# IM.net
KiCad netlist of a schematic drawn in Altium Designer
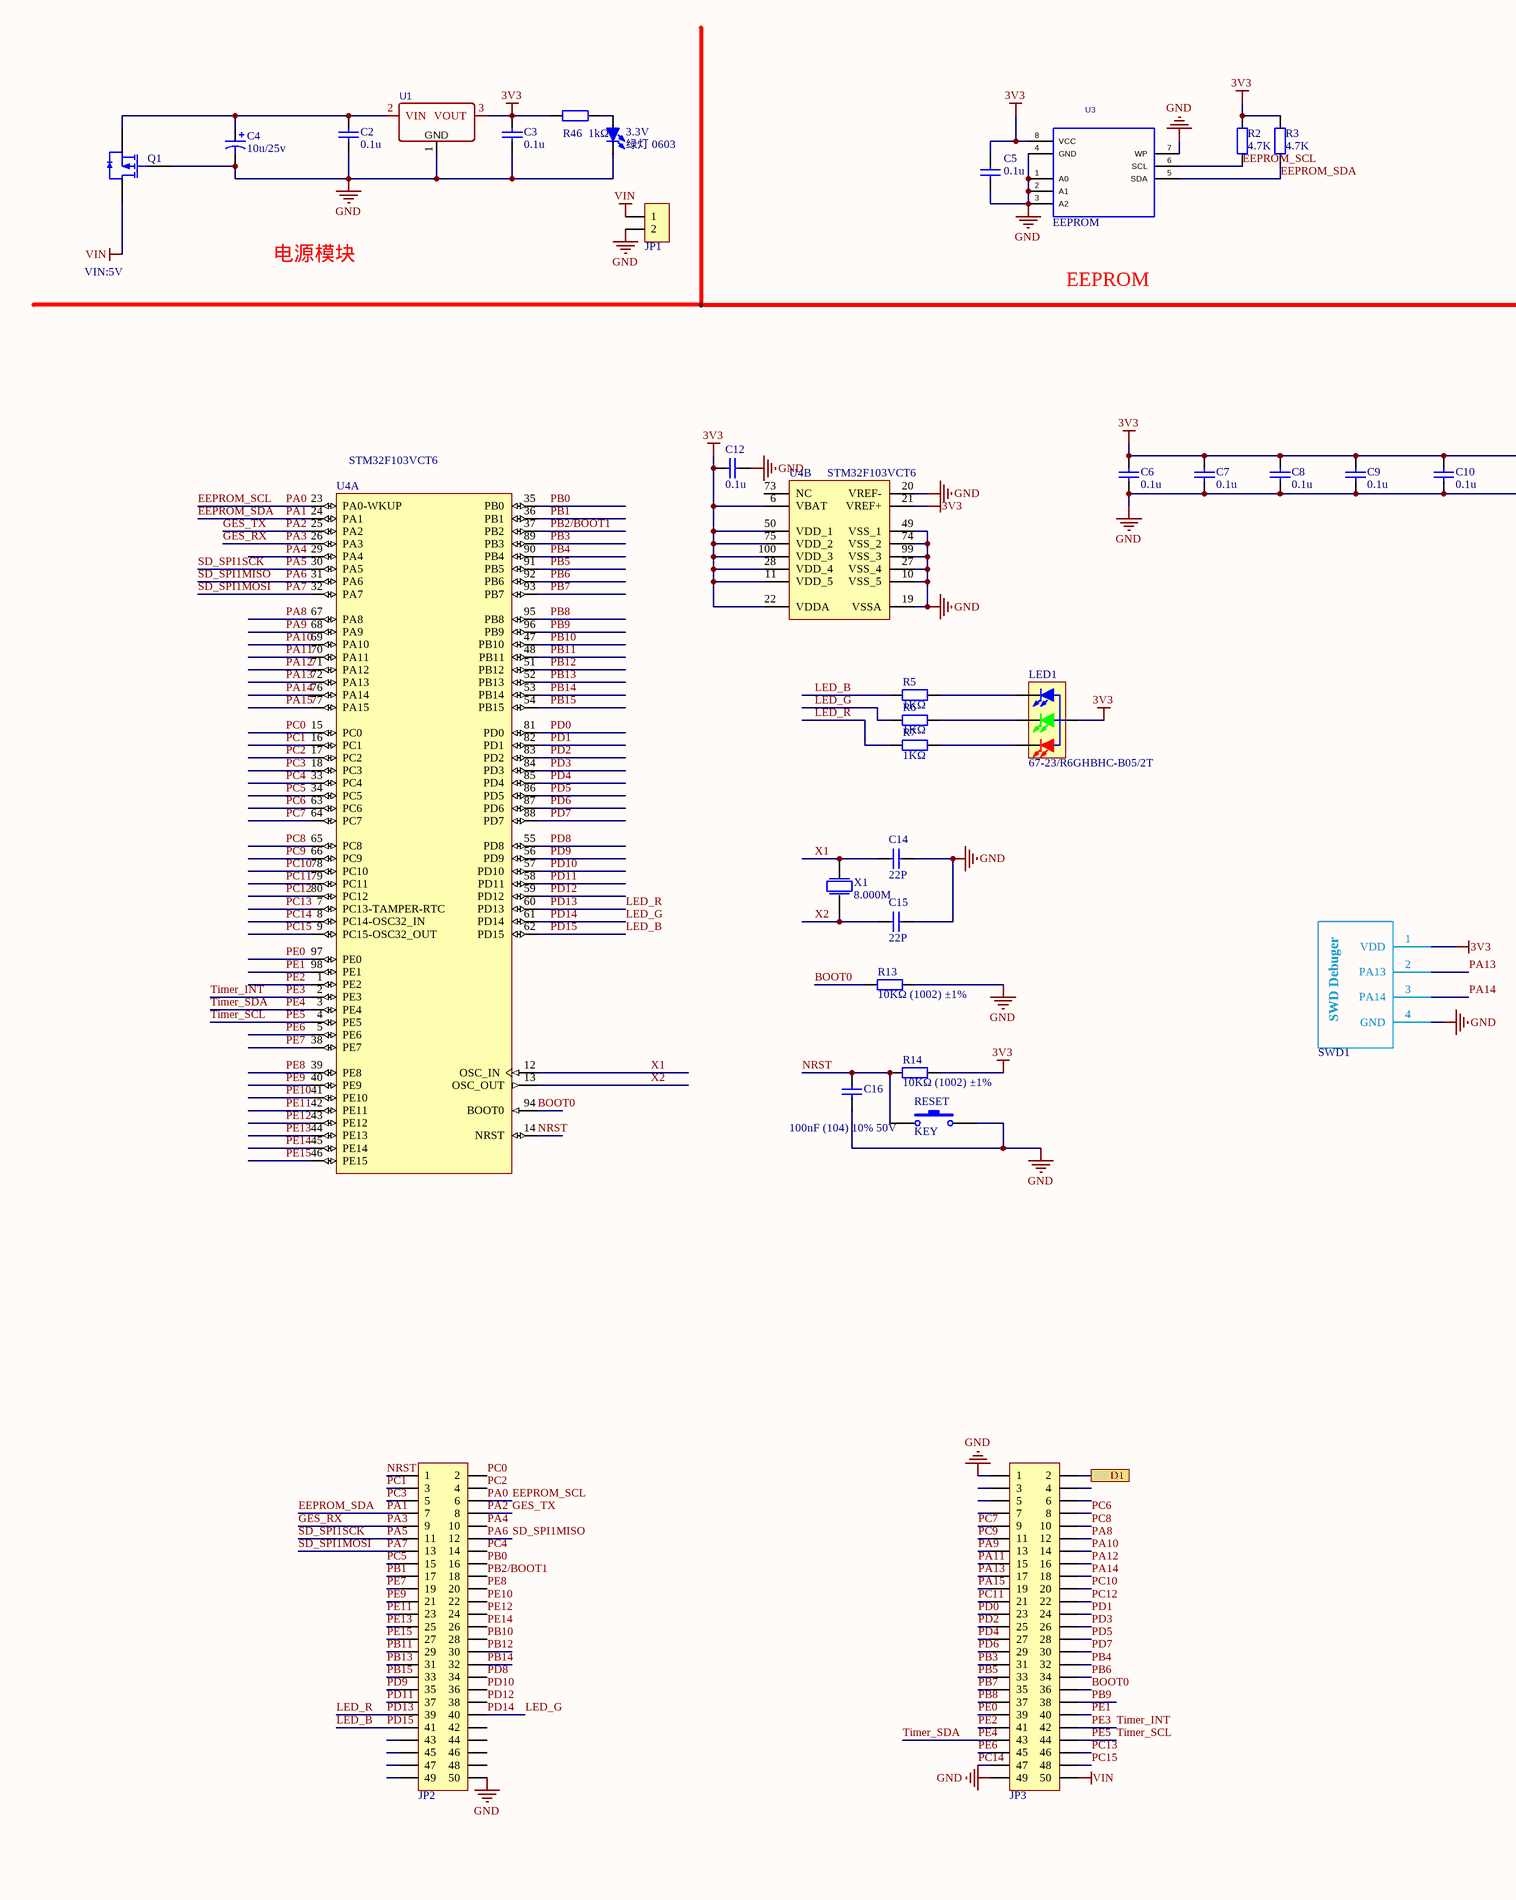
[diagram p0: IM.SchDoc, left]
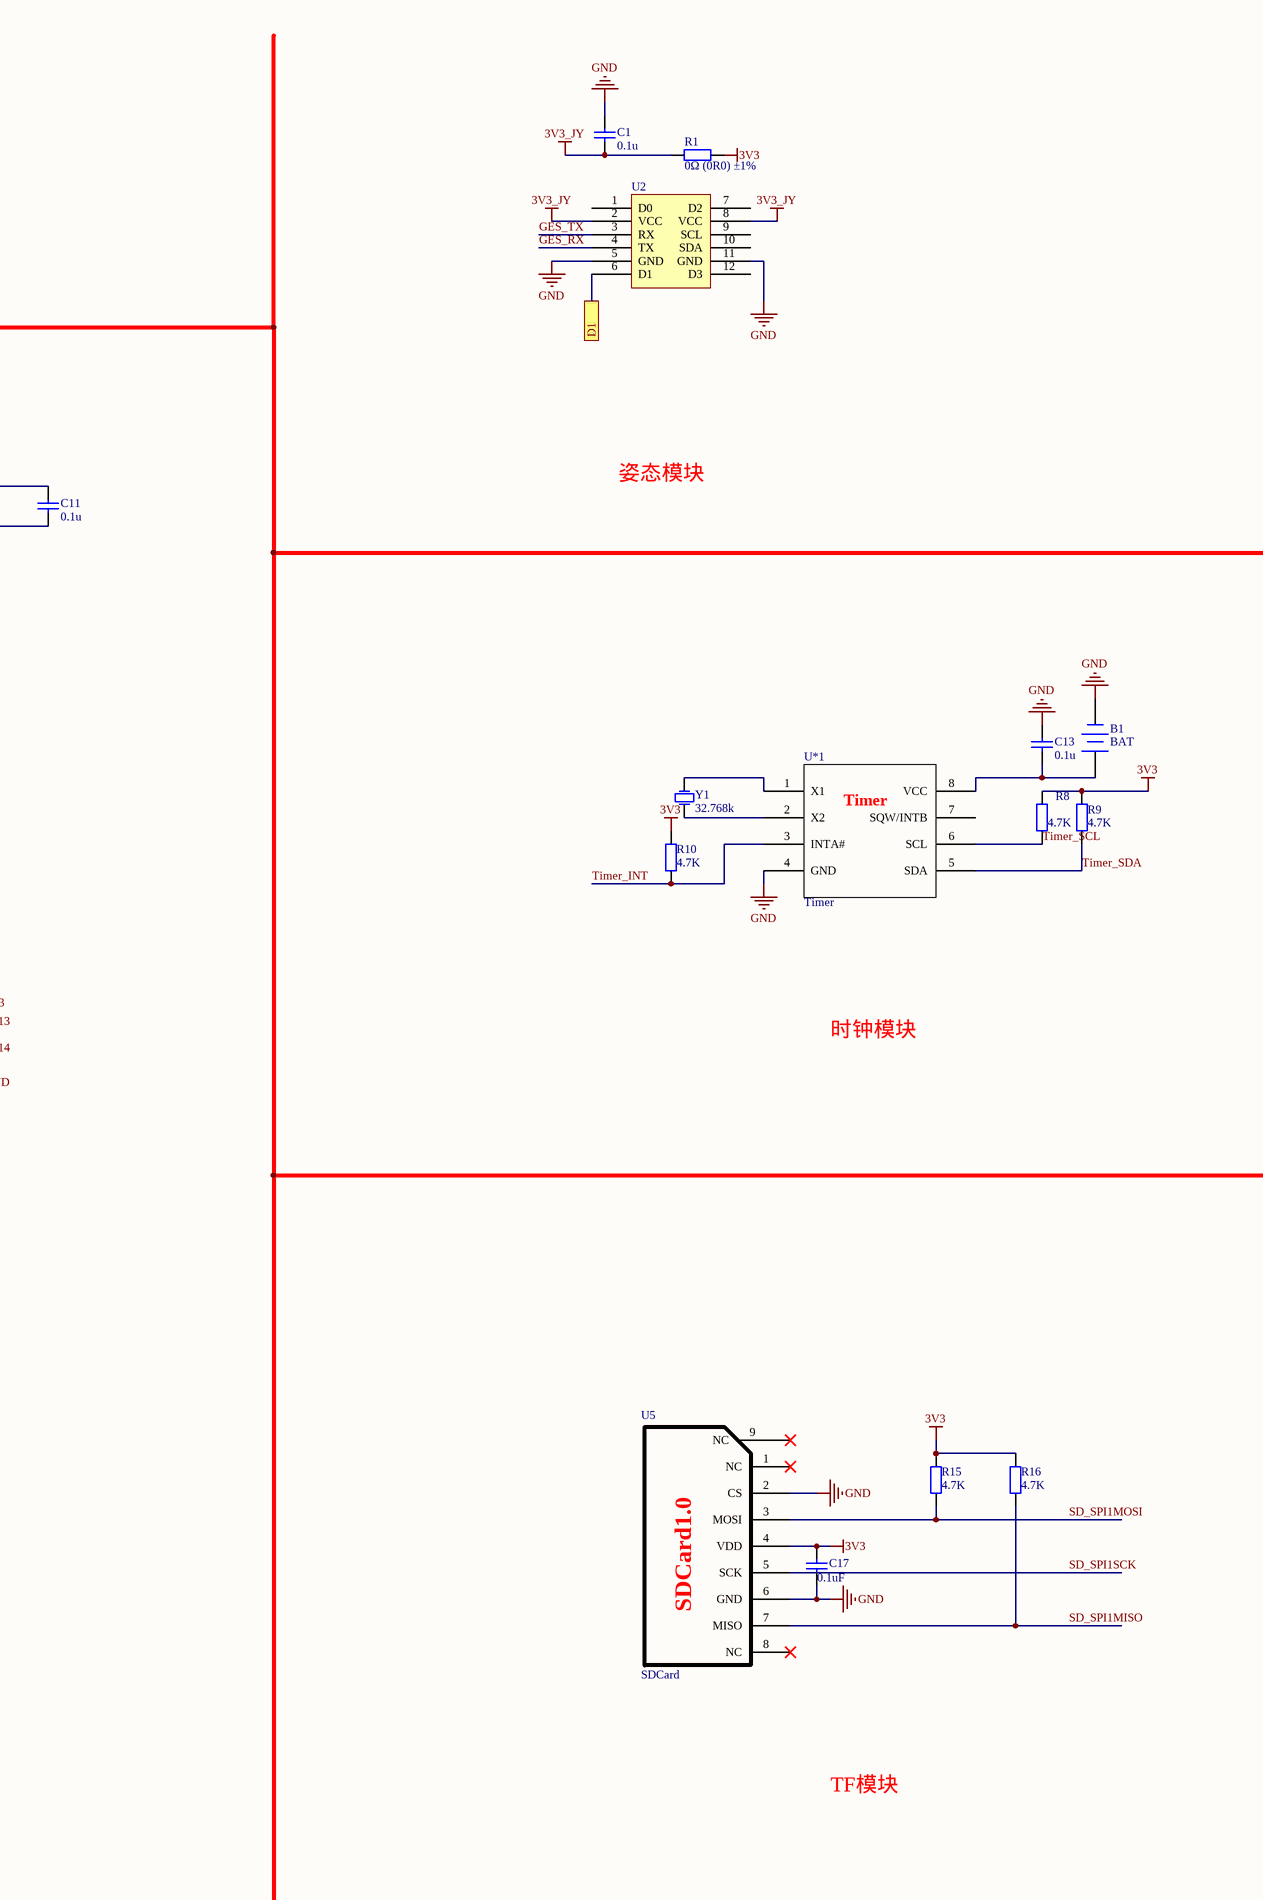
[diagram p1: IM.SchDoc, right]

(export (version "E")
  (design (tool "Eeschema 10.0.6"))
  (components
    (comp (ref "3.3V")
      (value "绿灯 0603")
      (footprint "0603_LED")
      (description "贴片LED")
      (libsource (lib "5-LED") (part "0603 LED"))
    )
    (comp (ref "B1") (value "BAT") (footprint "BAT") (libsource (lib "NewMag") (part "BAT")))
    (comp (ref "C1") (value "0.1u") (footprint "0603_C") (libsource (lib "ANSJ") (part "CAP0805")))
    (comp (ref "C2") (value "0.1u") (footprint "0603_C") (libsource (lib "ANSJ") (part "CAP0805")))
    (comp (ref "C3") (value "0.1u") (footprint "0603_C") (libsource (lib "ANSJ") (part "CAP0805")))
    (comp (ref "C4") (value "10u/25v") (footprint "SMD-3225-2P") (libsource (lib "NewMag") (part "CAP[B]")))
    (comp (ref "C5") (value "0.1u") (footprint "0603_C") (libsource (lib "ANSJ") (part "CAP0805")))
    (comp (ref "C6") (value "0.1u") (footprint "0603_C") (libsource (lib "ANSJ") (part "CAP0805")))
    (comp (ref "C7") (value "0.1u") (footprint "0603_C") (libsource (lib "ANSJ") (part "CAP0805")))
    (comp (ref "C8") (value "0.1u") (footprint "0603_C") (libsource (lib "ANSJ") (part "CAP0805")))
    (comp (ref "C9") (value "0.1u") (footprint "0603_C") (libsource (lib "ANSJ") (part "CAP0805")))
    (comp (ref "C10") (value "0.1u") (footprint "0603_C") (libsource (lib "ANSJ") (part "CAP0805")))
    (comp (ref "C11") (value "0.1u") (footprint "0603_C") (libsource (lib "ANSJ") (part "CAP0805")))
    (comp (ref "C12") (value "0.1u") (footprint "0603_C") (libsource (lib "ANSJ") (part "CAP0805")))
    (comp (ref "C13") (value "0.1u") (footprint "0603_C") (libsource (lib "ANSJ") (part "CAP0805")))
    (comp (ref "C14") (value "22P") (footprint "0603_C") (libsource (lib "ANSJ") (part "CAP0805")))
    (comp (ref "C15") (value "22P") (footprint "0603_C") (libsource (lib "ANSJ") (part "CAP0805")))
    (comp (ref "C16")
      (value "100nF (104) 10% 50V")
      (footprint "0603_C")
      (description "贴片电容")
      (libsource (lib "Cap") (part "0603 100nF (104) 10% 50V"))
    )
    (comp (ref "C17") (value "0.1uF") (footprint "0603_C") (libsource (lib "ANSJ") (part "CAP0805")))
    (comp (ref "JP1")
      (value "HDR-1X2")
      (footprint "HDR2.54-LI-2P")
      (description "2P接插件")
      (fields (field (name "版权归属") "源创客"))
      (libsource (lib "12-Connector") (part "Header 2 Pitch2.54"))
    )
    (comp (ref "JP2")
      (value "Header 2X25")
      (footprint "HDR2.54-LI-2X25P")
      (description "25*2P接插件")
      (fields (field (name "版权归属") "源创客"))
      (libsource (lib "12-Connector") (part "Header 25X2 Pitch2.54"))
    )
    (comp (ref "JP3")
      (value "Header 2X25")
      (footprint "HDR2.54-LI-2X25P")
      (description "25*2P接插件")
      (fields (field (name "版权归属") "源创客"))
      (libsource (lib "12-Connector") (part "Header 25X2 Pitch2.54"))
    )
    (comp (ref "LED1")
      (value "67-23/R6GHBHC-B05/2T")
      (footprint "LED 3528-4Pin")
      (description "三基色LED")
      (fields (field (name "版权归属") "源创客"))
      (libsource (lib "5-LED") (part "LED-RGB-3528"))
    )
    (comp (ref "Q1")
      (value "AO3401A P道沟")
      (footprint "SOT-23(SOT-23-3)")
      (description "MOS(场效应管)")
      (libsource (lib "Miscellaneous Devices LC") (part "AO3401A P道沟 X13A15 SOT-23"))
    )
    (comp (ref "R1")
      (value "0Ω (0R0) ±1%")
      (footprint "0603_R")
      (description "贴片电阻")
      (libsource (lib "1-RES") (part "0603 0Ω (0R0) 1%"))
    )
    (comp (ref "R2") (value "4.7K") (footprint "0603_R") (libsource (lib "ANSJ") (part "RES0805")))
    (comp (ref "R3") (value "4.7K") (footprint "0603_R") (libsource (lib "ANSJ") (part "RES0805")))
    (comp (ref "R5")
      (value "1KΩ")
      (footprint "0603_R")
      (description "贴片电阻")
      (libsource (lib "1-RES") (part "0603 2.2KΩ (2201) 1%"))
    )
    (comp (ref "R6")
      (value "1KΩ")
      (footprint "0603_R")
      (description "贴片电阻")
      (libsource (lib "1-RES") (part "0603 2.2KΩ (2201) 1%"))
    )
    (comp (ref "R7")
      (value "1KΩ")
      (footprint "0603_R")
      (description "贴片电阻")
      (libsource (lib "1-RES") (part "0603 2.2KΩ (2201) 1%"))
    )
    (comp (ref "R8") (value "4.7K") (footprint "0603_R") (libsource (lib "") (part "RES0805_1")))
    (comp (ref "R9") (value "4.7K") (footprint "0603_R") (libsource (lib "") (part "RES0805_1")))
    (comp (ref "R10") (value "4.7K") (footprint "0603_R") (libsource (lib "") (part "RES0805_1")))
    (comp (ref "R13")
      (value "10KΩ (1002) ±1%")
      (footprint "0603_R")
      (description "贴片电阻")
      (libsource (lib "RES") (part "0603 10KΩ (1002) 1%"))
    )
    (comp (ref "R14")
      (value "10KΩ (1002) ±1%")
      (footprint "0603_R")
      (description "贴片电阻")
      (libsource (lib "RES") (part "0603 10KΩ (1002) 1%"))
    )
    (comp (ref "R15") (value "4.7K") (footprint "0603_R") (libsource (lib "ANSJ") (part "RES0805")))
    (comp (ref "R16") (value "4.7K") (footprint "0603_R") (libsource (lib "ANSJ") (part "RES0805")))
    (comp (ref "R46")
      (value "1kΩ")
      (footprint "0603_R")
      (description "贴片电阻")
      (libsource (lib "1-RES") (part "0603 0Ω (0R0) 1%"))
    )
    (comp (ref "RESET")
      (value "KEY")
      (footprint "key-2")
      (description "Switch")
      (fields (field (name "PUBLISHER") "Altium Limited"))
      (libsource (lib "MYLAB") (part "KEY_2"))
    )
    (comp (ref "SWD1") (value "SWD") (footprint "HDR2.54-LI-4P") (libsource (lib "NewMag") (part "SWD")))
    (comp (ref "U*1") (value "Timer") (libsource (lib "SIGMA") (part "Timer")))
    (comp (ref "U1")
      (value "HT7533/ME6210A33PG")
      (footprint "SOT-89(SOT-89-3)")
      (description "低压差线性稳压(LDO)")
      (fields (field (name "BOM_MANUFACTURER PART") "HT7533") (field (name "BOM_SUPPLIER PART") "C89203"))
      (libsource (lib "8-LDO") (part "SOT-89 HT7533/ME6210A33PG"))
    )
    (comp (ref "U2")
      (value "JY901")
      (footprint "JY-901")
      (description "姿态模块")
      (libsource (lib "SIGMA") (part "JY61P/JY901B"))
    )
    (comp (ref "U3")
      (value "EEPROM")
      (footprint "SIGMA:SOP8_N")
      (description "8 lead ssop,2k/2048bits")
      (fields (field (name "Comment") "AT24C02"))
      (libsource (lib "SIGMA") (part "AT24C02"))
    )
    (comp (ref "U4")
      (value "STM32F103VCT6")
      (footprint "LQFP100 14x14_N")
      (libsource (lib "STMicroelectronics STM32 F1") (part "STM32F100VET6"))
    )
    (comp (ref "U5") (value "SDCard") (footprint "TF-Micro") (libsource (lib "NewMag") (part "SDCard")))
    (comp (ref "X1") (value "8.000M") (footprint "OSC 5032-2P") (libsource (lib "NewMag") (part "XTALSOP")))
    (comp (ref "Y1")
      (value "32.768k")
      (footprint "SIGMA:OSC 3215-2P")
      (description "Crystal Oscillator")
      (fields (field (name "Comment") "无源晶振") (field (name "PUBLISHER") "Altium Limited"))
      (libsource (lib "SIGMA") (part "XTAL"))
    )
  )
  (nets
    (net (code "1") (name "/BOOT0") (class "Default")
      (node (ref "JP3") (pin "36") (pinfunction "36_36") (pintype "passive"))
      (node (ref "R13") (pin "1") (pinfunction "1_1") (pintype "passive"))
      (node (ref "U4") (pin "94") (pinfunction "BOOT0_94") (pintype "input"))
    )
    (net (code "2") (name "/D1") (class "Default")
      (node (ref "JP3") (pin "2") (pinfunction "2_2") (pintype "passive"))
      (node (ref "U2") (pin "6") (pinfunction "D1_6") (pintype "passive"))
    )
    (net (code "3") (name "/EEPROM_SCL") (class "Default")
      (node (ref "JP2") (pin "6") (pinfunction "6_6") (pintype "passive"))
      (node (ref "R2") (pin "2") (pinfunction "2_2") (pintype "passive"))
      (node (ref "U3") (pin "6") (pinfunction "SCL_6") (pintype "passive"))
      (node (ref "U4") (pin "23") (pinfunction "PA0-WKUP_23") (pintype "bidirectional"))
    )
    (net (code "4") (name "/EEPROM_SDA") (class "Default")
      (node (ref "JP2") (pin "7") (pinfunction "7_7") (pintype "passive"))
      (node (ref "R3") (pin "2") (pinfunction "2_2") (pintype "passive"))
      (node (ref "U3") (pin "5") (pinfunction "SDA_5") (pintype "passive"))
      (node (ref "U4") (pin "24") (pinfunction "PA1_24") (pintype "bidirectional"))
    )
    (net (code "5") (name "/GES_RX") (class "Default")
      (node (ref "JP2") (pin "9") (pinfunction "9_9") (pintype "passive"))
      (node (ref "U2") (pin "4") (pinfunction "TX_4") (pintype "passive"))
      (node (ref "U4") (pin "26") (pinfunction "PA3_26") (pintype "bidirectional"))
    )
    (net (code "6") (name "/GES_TX") (class "Default")
      (node (ref "JP2") (pin "8") (pinfunction "8_8") (pintype "passive"))
      (node (ref "U2") (pin "3") (pinfunction "RX_3") (pintype "passive"))
      (node (ref "U4") (pin "25") (pinfunction "PA2_25") (pintype "bidirectional"))
    )
    (net (code "7") (name "/LED_B") (class "Default")
      (node (ref "JP2") (pin "41") (pinfunction "41_41") (pintype "passive"))
      (node (ref "R5") (pin "1") (pinfunction "1_1") (pintype "passive"))
      (node (ref "U4") (pin "62") (pinfunction "PD15_62") (pintype "bidirectional"))
    )
    (net (code "8") (name "/LED_G") (class "Default")
      (node (ref "JP2") (pin "40") (pinfunction "40_40") (pintype "passive"))
      (node (ref "R6") (pin "1") (pinfunction "1_1") (pintype "passive"))
      (node (ref "U4") (pin "61") (pinfunction "PD14_61") (pintype "bidirectional"))
    )
    (net (code "9") (name "/LED_R") (class "Default")
      (node (ref "JP2") (pin "39") (pinfunction "39_39") (pintype "passive"))
      (node (ref "R7") (pin "1") (pinfunction "1_1") (pintype "passive"))
      (node (ref "U4") (pin "60") (pinfunction "PD13_60") (pintype "bidirectional"))
    )
    (net (code "10") (name "/NRST") (class "Default")
      (node (ref "C16") (pin "2") (pinfunction "2_2") (pintype "passive"))
      (node (ref "JP2") (pin "1") (pinfunction "1_1") (pintype "passive"))
      (node (ref "R14") (pin "1") (pinfunction "1_1") (pintype "passive"))
      (node (ref "RESET") (pin "1") (pinfunction "1_1") (pintype "passive"))
      (node (ref "U4") (pin "14") (pinfunction "NRST_14") (pintype "bidirectional"))
    )
    (net (code "11") (name "/PA4") (class "Default")
      (node (ref "JP2") (pin "10") (pinfunction "10_10") (pintype "passive"))
      (node (ref "U4") (pin "29") (pinfunction "PA4_29") (pintype "bidirectional"))
    )
    (net (code "12") (name "/PA5") (class "Default")
      (node (ref "JP2") (pin "11") (pinfunction "11_11") (pintype "passive"))
      (node (ref "U4") (pin "30") (pinfunction "PA5_30") (pintype "bidirectional"))
      (node (ref "U5") (pin "5") (pinfunction "SCK_5") (pintype "passive"))
    )
    (net (code "13") (name "/PA6") (class "Default")
      (node (ref "JP2") (pin "12") (pinfunction "12_12") (pintype "passive"))
      (node (ref "R16") (pin "2") (pinfunction "2_2") (pintype "passive"))
      (node (ref "U4") (pin "31") (pinfunction "PA6_31") (pintype "bidirectional"))
      (node (ref "U5") (pin "7") (pinfunction "MISO_7") (pintype "passive"))
    )
    (net (code "14") (name "/PA7") (class "Default")
      (node (ref "JP2") (pin "13") (pinfunction "13_13") (pintype "passive"))
      (node (ref "R15") (pin "2") (pinfunction "2_2") (pintype "passive"))
      (node (ref "U4") (pin "32") (pinfunction "PA7_32") (pintype "bidirectional"))
      (node (ref "U5") (pin "3") (pinfunction "MOSI_3") (pintype "passive"))
    )
    (net (code "15") (name "/PA8") (class "Default")
      (node (ref "JP3") (pin "12") (pinfunction "12_12") (pintype "passive"))
      (node (ref "U4") (pin "67") (pinfunction "PA8_67") (pintype "bidirectional"))
    )
    (net (code "16") (name "/PA9") (class "Default")
      (node (ref "JP3") (pin "13") (pinfunction "13_13") (pintype "passive"))
      (node (ref "U4") (pin "68") (pinfunction "PA9_68") (pintype "bidirectional"))
    )
    (net (code "17") (name "/PA10") (class "Default")
      (node (ref "JP3") (pin "14") (pinfunction "14_14") (pintype "passive"))
      (node (ref "U4") (pin "69") (pinfunction "PA10_69") (pintype "bidirectional"))
    )
    (net (code "18") (name "/PA11") (class "Default")
      (node (ref "JP3") (pin "15") (pinfunction "15_15") (pintype "passive"))
      (node (ref "U4") (pin "70") (pinfunction "PA11_70") (pintype "bidirectional"))
    )
    (net (code "19") (name "/PA12") (class "Default")
      (node (ref "JP3") (pin "16") (pinfunction "16_16") (pintype "passive"))
      (node (ref "U4") (pin "71") (pinfunction "PA12_71") (pintype "bidirectional"))
    )
    (net (code "20") (name "/PA13") (class "Default")
      (node (ref "JP3") (pin "17") (pinfunction "17_17") (pintype "passive"))
      (node (ref "SWD1") (pin "2") (pinfunction "PA13_2") (pintype "passive"))
      (node (ref "U4") (pin "72") (pinfunction "PA13_72") (pintype "bidirectional"))
    )
    (net (code "21") (name "/PA14") (class "Default")
      (node (ref "JP3") (pin "18") (pinfunction "18_18") (pintype "passive"))
      (node (ref "SWD1") (pin "3") (pinfunction "PA14_3") (pintype "passive"))
      (node (ref "U4") (pin "76") (pinfunction "PA14_76") (pintype "bidirectional"))
    )
    (net (code "22") (name "/PA15") (class "Default")
      (node (ref "JP3") (pin "19") (pinfunction "19_19") (pintype "passive"))
      (node (ref "U4") (pin "77") (pinfunction "PA15_77") (pintype "bidirectional"))
    )
    (net (code "23") (name "/PB0") (class "Default")
      (node (ref "JP2") (pin "16") (pinfunction "16_16") (pintype "passive"))
      (node (ref "U4") (pin "35") (pinfunction "PB0_35") (pintype "bidirectional"))
    )
    (net (code "24") (name "/PB1") (class "Default")
      (node (ref "JP2") (pin "17") (pinfunction "17_17") (pintype "passive"))
      (node (ref "U4") (pin "36") (pinfunction "PB1_36") (pintype "bidirectional"))
    )
    (net (code "25") (name "/PB2{slash}BOOT1") (class "Default")
      (node (ref "JP2") (pin "18") (pinfunction "18_18") (pintype "passive"))
      (node (ref "U4") (pin "37") (pinfunction "PB2_37") (pintype "bidirectional"))
    )
    (net (code "26") (name "/PB3") (class "Default")
      (node (ref "JP3") (pin "31") (pinfunction "31_31") (pintype "passive"))
      (node (ref "U4") (pin "89") (pinfunction "PB3_89") (pintype "bidirectional"))
    )
    (net (code "27") (name "/PB4") (class "Default")
      (node (ref "JP3") (pin "32") (pinfunction "32_32") (pintype "passive"))
      (node (ref "U4") (pin "90") (pinfunction "PB4_90") (pintype "bidirectional"))
    )
    (net (code "28") (name "/PB5") (class "Default")
      (node (ref "JP3") (pin "33") (pinfunction "33_33") (pintype "passive"))
      (node (ref "U4") (pin "91") (pinfunction "PB5_91") (pintype "bidirectional"))
    )
    (net (code "29") (name "/PB6") (class "Default")
      (node (ref "JP3") (pin "34") (pinfunction "34_34") (pintype "passive"))
      (node (ref "U4") (pin "92") (pinfunction "PB6_92") (pintype "bidirectional"))
    )
    (net (code "30") (name "/PB7") (class "Default")
      (node (ref "JP3") (pin "35") (pinfunction "35_35") (pintype "passive"))
      (node (ref "U4") (pin "93") (pinfunction "PB7_93") (pintype "bidirectional"))
    )
    (net (code "31") (name "/PB8") (class "Default")
      (node (ref "JP3") (pin "37") (pinfunction "37_37") (pintype "passive"))
      (node (ref "U4") (pin "95") (pinfunction "PB8_95") (pintype "bidirectional"))
    )
    (net (code "32") (name "/PB9") (class "Default")
      (node (ref "JP3") (pin "38") (pinfunction "38_38") (pintype "passive"))
      (node (ref "U4") (pin "96") (pinfunction "PB9_96") (pintype "bidirectional"))
    )
    (net (code "33") (name "/PB10") (class "Default")
      (node (ref "JP2") (pin "28") (pinfunction "28_28") (pintype "passive"))
      (node (ref "U4") (pin "47") (pinfunction "PB10_47") (pintype "bidirectional"))
    )
    (net (code "34") (name "/PB11") (class "Default")
      (node (ref "JP2") (pin "29") (pinfunction "29_29") (pintype "passive"))
      (node (ref "U4") (pin "48") (pinfunction "PB11_48") (pintype "bidirectional"))
    )
    (net (code "35") (name "/PB12") (class "Default")
      (node (ref "JP2") (pin "30") (pinfunction "30_30") (pintype "passive"))
      (node (ref "U4") (pin "51") (pinfunction "PB12_51") (pintype "bidirectional"))
    )
    (net (code "36") (name "/PB13") (class "Default")
      (node (ref "JP2") (pin "31") (pinfunction "31_31") (pintype "passive"))
      (node (ref "U4") (pin "52") (pinfunction "PB13_52") (pintype "bidirectional"))
    )
    (net (code "37") (name "/PB14") (class "Default")
      (node (ref "JP2") (pin "32") (pinfunction "32_32") (pintype "passive"))
      (node (ref "U4") (pin "53") (pinfunction "PB14_53") (pintype "bidirectional"))
    )
    (net (code "38") (name "/PB15") (class "Default")
      (node (ref "JP2") (pin "33") (pinfunction "33_33") (pintype "passive"))
      (node (ref "U4") (pin "54") (pinfunction "PB15_54") (pintype "bidirectional"))
    )
    (net (code "39") (name "/PC0") (class "Default")
      (node (ref "JP2") (pin "2") (pinfunction "2_2") (pintype "passive"))
      (node (ref "U4") (pin "15") (pinfunction "PC0_15") (pintype "bidirectional"))
    )
    (net (code "40") (name "/PC1") (class "Default")
      (node (ref "JP2") (pin "3") (pinfunction "3_3") (pintype "passive"))
      (node (ref "U4") (pin "16") (pinfunction "PC1_16") (pintype "bidirectional"))
    )
    (net (code "41") (name "/PC2") (class "Default")
      (node (ref "JP2") (pin "4") (pinfunction "4_4") (pintype "passive"))
      (node (ref "U4") (pin "17") (pinfunction "PC2_17") (pintype "bidirectional"))
    )
    (net (code "42") (name "/PC3") (class "Default")
      (node (ref "JP2") (pin "5") (pinfunction "5_5") (pintype "passive"))
      (node (ref "U4") (pin "18") (pinfunction "PC3_18") (pintype "bidirectional"))
    )
    (net (code "43") (name "/PC4") (class "Default")
      (node (ref "JP2") (pin "14") (pinfunction "14_14") (pintype "passive"))
      (node (ref "U4") (pin "33") (pinfunction "PC4_33") (pintype "bidirectional"))
    )
    (net (code "44") (name "/PC5") (class "Default")
      (node (ref "JP2") (pin "15") (pinfunction "15_15") (pintype "passive"))
      (node (ref "U4") (pin "34") (pinfunction "PC5_34") (pintype "bidirectional"))
    )
    (net (code "45") (name "/PC6") (class "Default")
      (node (ref "JP3") (pin "8") (pinfunction "8_8") (pintype "passive"))
      (node (ref "U4") (pin "63") (pinfunction "PC6_63") (pintype "bidirectional"))
    )
    (net (code "46") (name "/PC7") (class "Default")
      (node (ref "JP3") (pin "9") (pinfunction "9_9") (pintype "passive"))
      (node (ref "U4") (pin "64") (pinfunction "PC7_64") (pintype "bidirectional"))
    )
    (net (code "47") (name "/PC8") (class "Default")
      (node (ref "JP3") (pin "10") (pinfunction "10_10") (pintype "passive"))
      (node (ref "U4") (pin "65") (pinfunction "PC8_65") (pintype "bidirectional"))
    )
    (net (code "48") (name "/PC9") (class "Default")
      (node (ref "JP3") (pin "11") (pinfunction "11_11") (pintype "passive"))
      (node (ref "U4") (pin "66") (pinfunction "PC9_66") (pintype "bidirectional"))
    )
    (net (code "49") (name "/PC10") (class "Default")
      (node (ref "JP3") (pin "20") (pinfunction "20_20") (pintype "passive"))
      (node (ref "U4") (pin "78") (pinfunction "PC10_78") (pintype "bidirectional"))
    )
    (net (code "50") (name "/PC11") (class "Default")
      (node (ref "JP3") (pin "21") (pinfunction "21_21") (pintype "passive"))
      (node (ref "U4") (pin "79") (pinfunction "PC11_79") (pintype "bidirectional"))
    )
    (net (code "51") (name "/PC12") (class "Default")
      (node (ref "JP3") (pin "22") (pinfunction "22_22") (pintype "passive"))
      (node (ref "U4") (pin "80") (pinfunction "PC12_80") (pintype "bidirectional"))
    )
    (net (code "52") (name "/PC13") (class "Default")
      (node (ref "JP3") (pin "46") (pinfunction "46_46") (pintype "passive"))
      (node (ref "U4") (pin "7") (pinfunction "PC13-TAMPER-RTC_7") (pintype "bidirectional"))
    )
    (net (code "53") (name "/PC14") (class "Default")
      (node (ref "JP3") (pin "47") (pinfunction "47_47") (pintype "passive"))
      (node (ref "U4") (pin "8") (pinfunction "PC14-OSC32_IN_8") (pintype "bidirectional"))
    )
    (net (code "54") (name "/PC15") (class "Default")
      (node (ref "JP3") (pin "48") (pinfunction "48_48") (pintype "passive"))
      (node (ref "U4") (pin "9") (pinfunction "PC15-OSC32_OUT_9") (pintype "bidirectional"))
    )
    (net (code "55") (name "/PD0") (class "Default")
      (node (ref "JP3") (pin "23") (pinfunction "23_23") (pintype "passive"))
      (node (ref "U4") (pin "81") (pinfunction "PD0_81") (pintype "bidirectional"))
    )
    (net (code "56") (name "/PD1") (class "Default")
      (node (ref "JP3") (pin "24") (pinfunction "24_24") (pintype "passive"))
      (node (ref "U4") (pin "82") (pinfunction "PD1_82") (pintype "bidirectional"))
    )
    (net (code "57") (name "/PD2") (class "Default")
      (node (ref "JP3") (pin "25") (pinfunction "25_25") (pintype "passive"))
      (node (ref "U4") (pin "83") (pinfunction "PD2_83") (pintype "bidirectional"))
    )
    (net (code "58") (name "/PD3") (class "Default")
      (node (ref "JP3") (pin "26") (pinfunction "26_26") (pintype "passive"))
      (node (ref "U4") (pin "84") (pinfunction "PD3_84") (pintype "bidirectional"))
    )
    (net (code "59") (name "/PD4") (class "Default")
      (node (ref "JP3") (pin "27") (pinfunction "27_27") (pintype "passive"))
      (node (ref "U4") (pin "85") (pinfunction "PD4_85") (pintype "bidirectional"))
    )
    (net (code "60") (name "/PD5") (class "Default")
      (node (ref "JP3") (pin "28") (pinfunction "28_28") (pintype "passive"))
      (node (ref "U4") (pin "86") (pinfunction "PD5_86") (pintype "bidirectional"))
    )
    (net (code "61") (name "/PD6") (class "Default")
      (node (ref "JP3") (pin "29") (pinfunction "29_29") (pintype "passive"))
      (node (ref "U4") (pin "87") (pinfunction "PD6_87") (pintype "bidirectional"))
    )
    (net (code "62") (name "/PD7") (class "Default")
      (node (ref "JP3") (pin "30") (pinfunction "30_30") (pintype "passive"))
      (node (ref "U4") (pin "88") (pinfunction "PD7_88") (pintype "bidirectional"))
    )
    (net (code "63") (name "/PD8") (class "Default")
      (node (ref "JP2") (pin "34") (pinfunction "34_34") (pintype "passive"))
      (node (ref "U4") (pin "55") (pinfunction "PD8_55") (pintype "bidirectional"))
    )
    (net (code "64") (name "/PD9") (class "Default")
      (node (ref "JP2") (pin "35") (pinfunction "35_35") (pintype "passive"))
      (node (ref "U4") (pin "56") (pinfunction "PD9_56") (pintype "bidirectional"))
    )
    (net (code "65") (name "/PD10") (class "Default")
      (node (ref "JP2") (pin "36") (pinfunction "36_36") (pintype "passive"))
      (node (ref "U4") (pin "57") (pinfunction "PD10_57") (pintype "bidirectional"))
    )
    (net (code "66") (name "/PD11") (class "Default")
      (node (ref "JP2") (pin "37") (pinfunction "37_37") (pintype "passive"))
      (node (ref "U4") (pin "58") (pinfunction "PD11_58") (pintype "bidirectional"))
    )
    (net (code "67") (name "/PD12") (class "Default")
      (node (ref "JP2") (pin "38") (pinfunction "38_38") (pintype "passive"))
      (node (ref "U4") (pin "59") (pinfunction "PD12_59") (pintype "bidirectional"))
    )
    (net (code "68") (name "/PE0") (class "Default")
      (node (ref "JP3") (pin "39") (pinfunction "39_39") (pintype "passive"))
      (node (ref "U4") (pin "97") (pinfunction "PE0_97") (pintype "bidirectional"))
    )
    (net (code "69") (name "/PE1") (class "Default")
      (node (ref "JP3") (pin "40") (pinfunction "40_40") (pintype "passive"))
      (node (ref "U4") (pin "98") (pinfunction "PE1_98") (pintype "bidirectional"))
    )
    (net (code "70") (name "/PE2") (class "Default")
      (node (ref "JP3") (pin "41") (pinfunction "41_41") (pintype "passive"))
      (node (ref "U4") (pin "1") (pinfunction "PE2_1") (pintype "bidirectional"))
    )
    (net (code "71") (name "/PE3") (class "Default")
      (node (ref "JP3") (pin "42") (pinfunction "42_42") (pintype "passive"))
      (node (ref "R10") (pin "1") (pinfunction "1_1") (pintype "passive"))
      (node (ref "U*1") (pin "3") (pinfunction "INTA#_3") (pintype "passive"))
      (node (ref "U4") (pin "2") (pinfunction "PE3_2") (pintype "bidirectional"))
    )
    (net (code "72") (name "/PE4") (class "Default")
      (node (ref "JP3") (pin "43") (pinfunction "43_43") (pintype "passive"))
      (node (ref "R9") (pin "1") (pinfunction "1_1") (pintype "passive"))
      (node (ref "U*1") (pin "5") (pinfunction "SDA_5") (pintype "passive"))
      (node (ref "U4") (pin "3") (pinfunction "PE4_3") (pintype "bidirectional"))
    )
    (net (code "73") (name "/PE5") (class "Default")
      (node (ref "JP3") (pin "44") (pinfunction "44_44") (pintype "passive"))
      (node (ref "R8") (pin "1") (pinfunction "1_1") (pintype "passive"))
      (node (ref "U*1") (pin "6") (pinfunction "SCL_6") (pintype "passive"))
      (node (ref "U4") (pin "4") (pinfunction "PE5_4") (pintype "bidirectional"))
    )
    (net (code "74") (name "/PE6") (class "Default")
      (node (ref "JP3") (pin "45") (pinfunction "45_45") (pintype "passive"))
      (node (ref "U4") (pin "5") (pinfunction "PE6_5") (pintype "bidirectional"))
    )
    (net (code "75") (name "/PE7") (class "Default")
      (node (ref "JP2") (pin "19") (pinfunction "19_19") (pintype "passive"))
      (node (ref "U4") (pin "38") (pinfunction "PE7_38") (pintype "bidirectional"))
    )
    (net (code "76") (name "/PE8") (class "Default")
      (node (ref "JP2") (pin "20") (pinfunction "20_20") (pintype "passive"))
      (node (ref "U4") (pin "39") (pinfunction "PE8_39") (pintype "bidirectional"))
    )
    (net (code "77") (name "/PE9") (class "Default")
      (node (ref "JP2") (pin "21") (pinfunction "21_21") (pintype "passive"))
      (node (ref "U4") (pin "40") (pinfunction "PE9_40") (pintype "bidirectional"))
    )
    (net (code "78") (name "/PE10") (class "Default")
      (node (ref "JP2") (pin "22") (pinfunction "22_22") (pintype "passive"))
      (node (ref "U4") (pin "41") (pinfunction "PE10_41") (pintype "bidirectional"))
    )
    (net (code "79") (name "/PE11") (class "Default")
      (node (ref "JP2") (pin "23") (pinfunction "23_23") (pintype "passive"))
      (node (ref "U4") (pin "42") (pinfunction "PE11_42") (pintype "bidirectional"))
    )
    (net (code "80") (name "/PE12") (class "Default")
      (node (ref "JP2") (pin "24") (pinfunction "24_24") (pintype "passive"))
      (node (ref "U4") (pin "43") (pinfunction "PE12_43") (pintype "bidirectional"))
    )
    (net (code "81") (name "/PE13") (class "Default")
      (node (ref "JP2") (pin "25") (pinfunction "25_25") (pintype "passive"))
      (node (ref "U4") (pin "44") (pinfunction "PE13_44") (pintype "bidirectional"))
    )
    (net (code "82") (name "/PE14") (class "Default")
      (node (ref "JP2") (pin "26") (pinfunction "26_26") (pintype "passive"))
      (node (ref "U4") (pin "45") (pinfunction "PE14_45") (pintype "bidirectional"))
    )
    (net (code "83") (name "/PE15") (class "Default")
      (node (ref "JP2") (pin "27") (pinfunction "27_27") (pintype "passive"))
      (node (ref "U4") (pin "46") (pinfunction "PE15_46") (pintype "bidirectional"))
    )
    (net (code "84") (name "/X1") (class "Default")
      (node (ref "C14") (pin "1") (pinfunction "1_1") (pintype "passive"))
      (node (ref "U4") (pin "12") (pinfunction "OSC_IN_12") (pintype "input"))
      (node (ref "X1") (pin "2") (pinfunction "2_2") (pintype "passive"))
    )
    (net (code "85") (name "/X2") (class "Default")
      (node (ref "C15") (pin "1") (pinfunction "1_1") (pintype "passive"))
      (node (ref "U4") (pin "13") (pinfunction "OSC_OUT_13") (pintype "output"))
      (node (ref "X1") (pin "1") (pinfunction "1_1") (pintype "passive"))
    )
    (net (code "86") (name "3V3") (class "Default")
      (node (ref "C10") (pin "2") (pinfunction "2_2") (pintype "passive"))
      (node (ref "C11") (pin "2") (pinfunction "2_2") (pintype "passive"))
      (node (ref "C12") (pin "1") (pinfunction "1_1") (pintype "passive"))
      (node (ref "C17") (pin "1") (pinfunction "1_1") (pintype "passive"))
      (node (ref "C3") (pin "2") (pinfunction "2_2") (pintype "passive"))
      (node (ref "C5") (pin "2") (pinfunction "2_2") (pintype "passive"))
      (node (ref "C6") (pin "2") (pinfunction "2_2") (pintype "passive"))
      (node (ref "C7") (pin "2") (pinfunction "2_2") (pintype "passive"))
      (node (ref "C8") (pin "2") (pinfunction "2_2") (pintype "passive"))
      (node (ref "C9") (pin "2") (pinfunction "2_2") (pintype "passive"))
      (node (ref "LED1") (pin "4") (pinfunction "A_4") (pintype "passive"))
      (node (ref "R1") (pin "2") (pinfunction "2_2") (pintype "passive"))
      (node (ref "R10") (pin "2") (pinfunction "2_2") (pintype "passive"))
      (node (ref "R14") (pin "2") (pinfunction "2_2") (pintype "passive"))
      (node (ref "R15") (pin "1") (pinfunction "1_1") (pintype "passive"))
      (node (ref "R16") (pin "1") (pinfunction "1_1") (pintype "passive"))
      (node (ref "R2") (pin "1") (pinfunction "1_1") (pintype "passive"))
      (node (ref "R3") (pin "1") (pinfunction "1_1") (pintype "passive"))
      (node (ref "R46") (pin "1") (pinfunction "1_1") (pintype "passive"))
      (node (ref "R8") (pin "2") (pinfunction "2_2") (pintype "passive"))
      (node (ref "R9") (pin "2") (pinfunction "2_2") (pintype "passive"))
      (node (ref "SWD1") (pin "1") (pinfunction "VDD_1") (pintype "passive"))
      (node (ref "U1") (pin "3") (pinfunction "VOUT_3") (pintype "passive"))
      (node (ref "U3") (pin "8") (pinfunction "VCC_8") (pintype "passive"))
      (node (ref "U4") (pin "100") (pinfunction "VDD_3_100") (pintype "power_in"))
      (node (ref "U4") (pin "11") (pinfunction "VDD_5_11") (pintype "power_in"))
      (node (ref "U4") (pin "21") (pinfunction "VREF+_21") (pintype "power_in"))
      (node (ref "U4") (pin "22") (pinfunction "VDDA_22") (pintype "power_in"))
      (node (ref "U4") (pin "28") (pinfunction "VDD_4_28") (pintype "power_in"))
      (node (ref "U4") (pin "50") (pinfunction "VDD_1_50") (pintype "power_in"))
      (node (ref "U4") (pin "6") (pinfunction "VBAT_6") (pintype "power_in"))
      (node (ref "U4") (pin "75") (pinfunction "VDD_2_75") (pintype "power_in"))
      (node (ref "U5") (pin "4") (pinfunction "VDD_4") (pintype "passive"))
    )
    (net (code "87") (name "3V3_JY") (class "Default")
      (node (ref "C1") (pin "1") (pinfunction "1_1") (pintype "passive"))
      (node (ref "R1") (pin "1") (pinfunction "1_1") (pintype "passive"))
      (node (ref "U2") (pin "2") (pinfunction "VCC_2") (pintype "passive"))
      (node (ref "U2") (pin "8") (pinfunction "VCC_8") (pintype "passive"))
    )
    (net (code "88") (name "GND") (class "Default")
      (node (ref "3.3V") (pin "K") (pinfunction "2_K") (pintype "passive"))
      (node (ref "B1") (pin "2") (pinfunction "-_2") (pintype "passive"))
      (node (ref "C1") (pin "2") (pinfunction "2_2") (pintype "passive"))
      (node (ref "C10") (pin "1") (pinfunction "1_1") (pintype "passive"))
      (node (ref "C11") (pin "1") (pinfunction "1_1") (pintype "passive"))
      (node (ref "C12") (pin "2") (pinfunction "2_2") (pintype "passive"))
      (node (ref "C13") (pin "2") (pinfunction "2_2") (pintype "passive"))
      (node (ref "C14") (pin "2") (pinfunction "2_2") (pintype "passive"))
      (node (ref "C15") (pin "2") (pinfunction "2_2") (pintype "passive"))
      (node (ref "C16") (pin "1") (pinfunction "1_1") (pintype "passive"))
      (node (ref "C17") (pin "2") (pinfunction "2_2") (pintype "passive"))
      (node (ref "C2") (pin "1") (pinfunction "1_1") (pintype "passive"))
      (node (ref "C3") (pin "1") (pinfunction "1_1") (pintype "passive"))
      (node (ref "C4") (pin "2") (pinfunction "2_2") (pintype "passive"))
      (node (ref "C5") (pin "1") (pinfunction "1_1") (pintype "passive"))
      (node (ref "C6") (pin "1") (pinfunction "1_1") (pintype "passive"))
      (node (ref "C7") (pin "1") (pinfunction "1_1") (pintype "passive"))
      (node (ref "C8") (pin "1") (pinfunction "1_1") (pintype "passive"))
      (node (ref "C9") (pin "1") (pinfunction "1_1") (pintype "passive"))
      (node (ref "JP1") (pin "2") (pinfunction "2_2") (pintype "passive"))
      (node (ref "JP2") (pin "50") (pinfunction "50_50") (pintype "passive"))
      (node (ref "JP3") (pin "1") (pinfunction "1_1") (pintype "passive"))
      (node (ref "JP3") (pin "49") (pinfunction "49_49") (pintype "passive"))
      (node (ref "Q1") (pin "1") (pinfunction "G_1") (pintype "passive"))
      (node (ref "R13") (pin "2") (pinfunction "2_2") (pintype "passive"))
      (node (ref "RESET") (pin "2") (pinfunction "2_2") (pintype "passive"))
      (node (ref "SWD1") (pin "4") (pinfunction "GND_4") (pintype "passive"))
      (node (ref "U*1") (pin "4") (pinfunction "GND_4") (pintype "passive"))
      (node (ref "U1") (pin "1") (pinfunction "GND_1") (pintype "passive"))
      (node (ref "U2") (pin "11") (pinfunction "GND_11") (pintype "passive"))
      (node (ref "U2") (pin "5") (pinfunction "GND_5") (pintype "passive"))
      (node (ref "U3") (pin "1") (pinfunction "A0_1") (pintype "passive"))
      (node (ref "U3") (pin "2") (pinfunction "A1_2") (pintype "passive"))
      (node (ref "U3") (pin "3") (pinfunction "A2_3") (pintype "passive"))
      (node (ref "U3") (pin "4") (pinfunction "GND_4") (pintype "passive"))
      (node (ref "U3") (pin "7") (pinfunction "WP_7") (pintype "passive"))
      (node (ref "U4") (pin "10") (pinfunction "VSS_5_10") (pintype "power_in"))
      (node (ref "U4") (pin "19") (pinfunction "VSSA_19") (pintype "power_in"))
      (node (ref "U4") (pin "20") (pinfunction "VREF-_20") (pintype "power_in"))
      (node (ref "U4") (pin "27") (pinfunction "VSS_4_27") (pintype "power_in"))
      (node (ref "U4") (pin "49") (pinfunction "VSS_1_49") (pintype "power_in"))
      (node (ref "U4") (pin "74") (pinfunction "VSS_2_74") (pintype "power_in"))
      (node (ref "U4") (pin "99") (pinfunction "VSS_3_99") (pintype "power_in"))
      (node (ref "U5") (pin "2") (pinfunction "CS_2") (pintype "passive"))
      (node (ref "U5") (pin "6") (pinfunction "GND_6") (pintype "passive"))
    )
    (net (code "89") (name "Net-(3.3V-1)") (class "Default")
      (node (ref "3.3V") (pin "A") (pinfunction "1_A") (pintype "passive"))
      (node (ref "R46") (pin "2") (pinfunction "2_2") (pintype "passive"))
    )
    (net (code "90") (name "Net-(B1-+)") (class "Default")
      (node (ref "B1") (pin "1") (pinfunction "+_1") (pintype "passive"))
      (node (ref "C13") (pin "1") (pinfunction "1_1") (pintype "passive"))
      (node (ref "U*1") (pin "8") (pinfunction "VCC_8") (pintype "passive"))
    )
    (net (code "91") (name "Net-(LED1-BULE_K)") (class "Default")
      (node (ref "LED1") (pin "3") (pinfunction "BULE_K_3") (pintype "passive"))
      (node (ref "R5") (pin "2") (pinfunction "2_2") (pintype "passive"))
    )
    (net (code "92") (name "Net-(LED1-GREEN_K)") (class "Default")
      (node (ref "LED1") (pin "2") (pinfunction "GREEN_K_2") (pintype "passive"))
      (node (ref "R6") (pin "2") (pinfunction "2_2") (pintype "passive"))
    )
    (net (code "93") (name "Net-(LED1-RED_K)") (class "Default")
      (node (ref "LED1") (pin "1") (pinfunction "RED_K_1") (pintype "passive"))
      (node (ref "R7") (pin "2") (pinfunction "2_2") (pintype "passive"))
    )
    (net (code "94") (name "Net-(Q1-S)") (class "Default")
      (node (ref "C2") (pin "2") (pinfunction "2_2") (pintype "passive"))
      (node (ref "C4") (pin "1") (pinfunction "1_1") (pintype "passive"))
      (node (ref "Q1") (pin "2") (pinfunction "S_2") (pintype "passive"))
      (node (ref "U1") (pin "2") (pinfunction "VIN_2") (pintype "passive"))
    )
    (net (code "95") (name "Net-(U*1-X1)") (class "Default")
      (node (ref "U*1") (pin "1") (pinfunction "X1_1") (pintype "passive"))
      (node (ref "Y1") (pin "2") (pinfunction "OSC2_2") (pintype "passive"))
    )
    (net (code "96") (name "Net-(U*1-X2)") (class "Default")
      (node (ref "U*1") (pin "2") (pinfunction "X2_2") (pintype "passive"))
      (node (ref "Y1") (pin "1") (pinfunction "OSC1_1") (pintype "passive"))
    )
    (net (code "97") (name "VIN") (class "Default")
      (node (ref "JP1") (pin "1") (pinfunction "1_1") (pintype "passive"))
      (node (ref "JP3") (pin "50") (pinfunction "50_50") (pintype "passive"))
      (node (ref "Q1") (pin "3") (pinfunction "D_3") (pintype "passive"))
    )
    (net (code "98") (name "unconnected-(JP2-Pad42)") (class "Default")
      (node (ref "JP2") (pin "42") (pinfunction "42_42") (pintype "passive"))
    )
    (net (code "99") (name "unconnected-(JP2-Pad43)") (class "Default")
      (node (ref "JP2") (pin "43") (pinfunction "43_43") (pintype "passive"))
    )
    (net (code "100") (name "unconnected-(JP2-Pad44)") (class "Default")
      (node (ref "JP2") (pin "44") (pinfunction "44_44") (pintype "passive"))
    )
    (net (code "101") (name "unconnected-(JP2-Pad45)") (class "Default")
      (node (ref "JP2") (pin "45") (pinfunction "45_45") (pintype "passive"))
    )
    (net (code "102") (name "unconnected-(JP2-Pad46)") (class "Default")
      (node (ref "JP2") (pin "46") (pinfunction "46_46") (pintype "passive"))
    )
    (net (code "103") (name "unconnected-(JP2-Pad47)") (class "Default")
      (node (ref "JP2") (pin "47") (pinfunction "47_47") (pintype "passive"))
    )
    (net (code "104") (name "unconnected-(JP2-Pad48)") (class "Default")
      (node (ref "JP2") (pin "48") (pinfunction "48_48") (pintype "passive"))
    )
    (net (code "105") (name "unconnected-(JP2-Pad49)") (class "Default")
      (node (ref "JP2") (pin "49") (pinfunction "49_49") (pintype "passive"))
    )
    (net (code "106") (name "unconnected-(JP3-Pad3)") (class "Default")
      (node (ref "JP3") (pin "3") (pinfunction "3_3") (pintype "passive"))
    )
    (net (code "107") (name "unconnected-(JP3-Pad4)") (class "Default")
      (node (ref "JP3") (pin "4") (pinfunction "4_4") (pintype "passive"))
    )
    (net (code "108") (name "unconnected-(JP3-Pad5)") (class "Default")
      (node (ref "JP3") (pin "5") (pinfunction "5_5") (pintype "passive"))
    )
    (net (code "109") (name "unconnected-(JP3-Pad6)") (class "Default")
      (node (ref "JP3") (pin "6") (pinfunction "6_6") (pintype "passive"))
    )
    (net (code "110") (name "unconnected-(JP3-Pad7)") (class "Default")
      (node (ref "JP3") (pin "7") (pinfunction "7_7") (pintype "passive"))
    )
    (net (code "111") (name "unconnected-(U*1-SQW{slash}INTB-Pad7)") (class "Default")
      (node (ref "U*1") (pin "7") (pinfunction "SQW/INTB_7") (pintype "passive"))
    )
    (net (code "112") (name "unconnected-(U2-D0-Pad1)") (class "Default")
      (node (ref "U2") (pin "1") (pinfunction "D0_1") (pintype "passive"))
    )
    (net (code "113") (name "unconnected-(U2-D2-Pad7)") (class "Default")
      (node (ref "U2") (pin "7") (pinfunction "D2_7") (pintype "passive"))
    )
    (net (code "114") (name "unconnected-(U2-D3-Pad12)") (class "Default")
      (node (ref "U2") (pin "12") (pinfunction "D3_12") (pintype "passive"))
    )
    (net (code "115") (name "unconnected-(U2-SCL-Pad9)") (class "Default")
      (node (ref "U2") (pin "9") (pinfunction "SCL_9") (pintype "passive"))
    )
    (net (code "116") (name "unconnected-(U2-SDA-Pad10)") (class "Default")
      (node (ref "U2") (pin "10") (pinfunction "SDA_10") (pintype "passive"))
    )
    (net (code "117") (name "unconnected-(U4B-NC-Pad73)") (class "Default")
      (node (ref "U4") (pin "73") (pinfunction "NC_73") (pintype "passive"))
    )
    (net (code "118") (name "unconnected-(U5-NC-Pad1)") (class "Default")
      (node (ref "U5") (pin "1") (pinfunction "NC_1") (pintype "passive+no_connect"))
    )
    (net (code "119") (name "unconnected-(U5-NC-Pad8)") (class "Default")
      (node (ref "U5") (pin "8") (pinfunction "NC_8") (pintype "passive+no_connect"))
    )
    (net (code "120") (name "unconnected-(U5-NC-Pad9)") (class "Default")
      (node (ref "U5") (pin "9") (pinfunction "NC_9") (pintype "passive+no_connect"))
    )
  )
)
